# port_expander_1_0.net
KiCad netlist of a schematic drawn in EAGLE
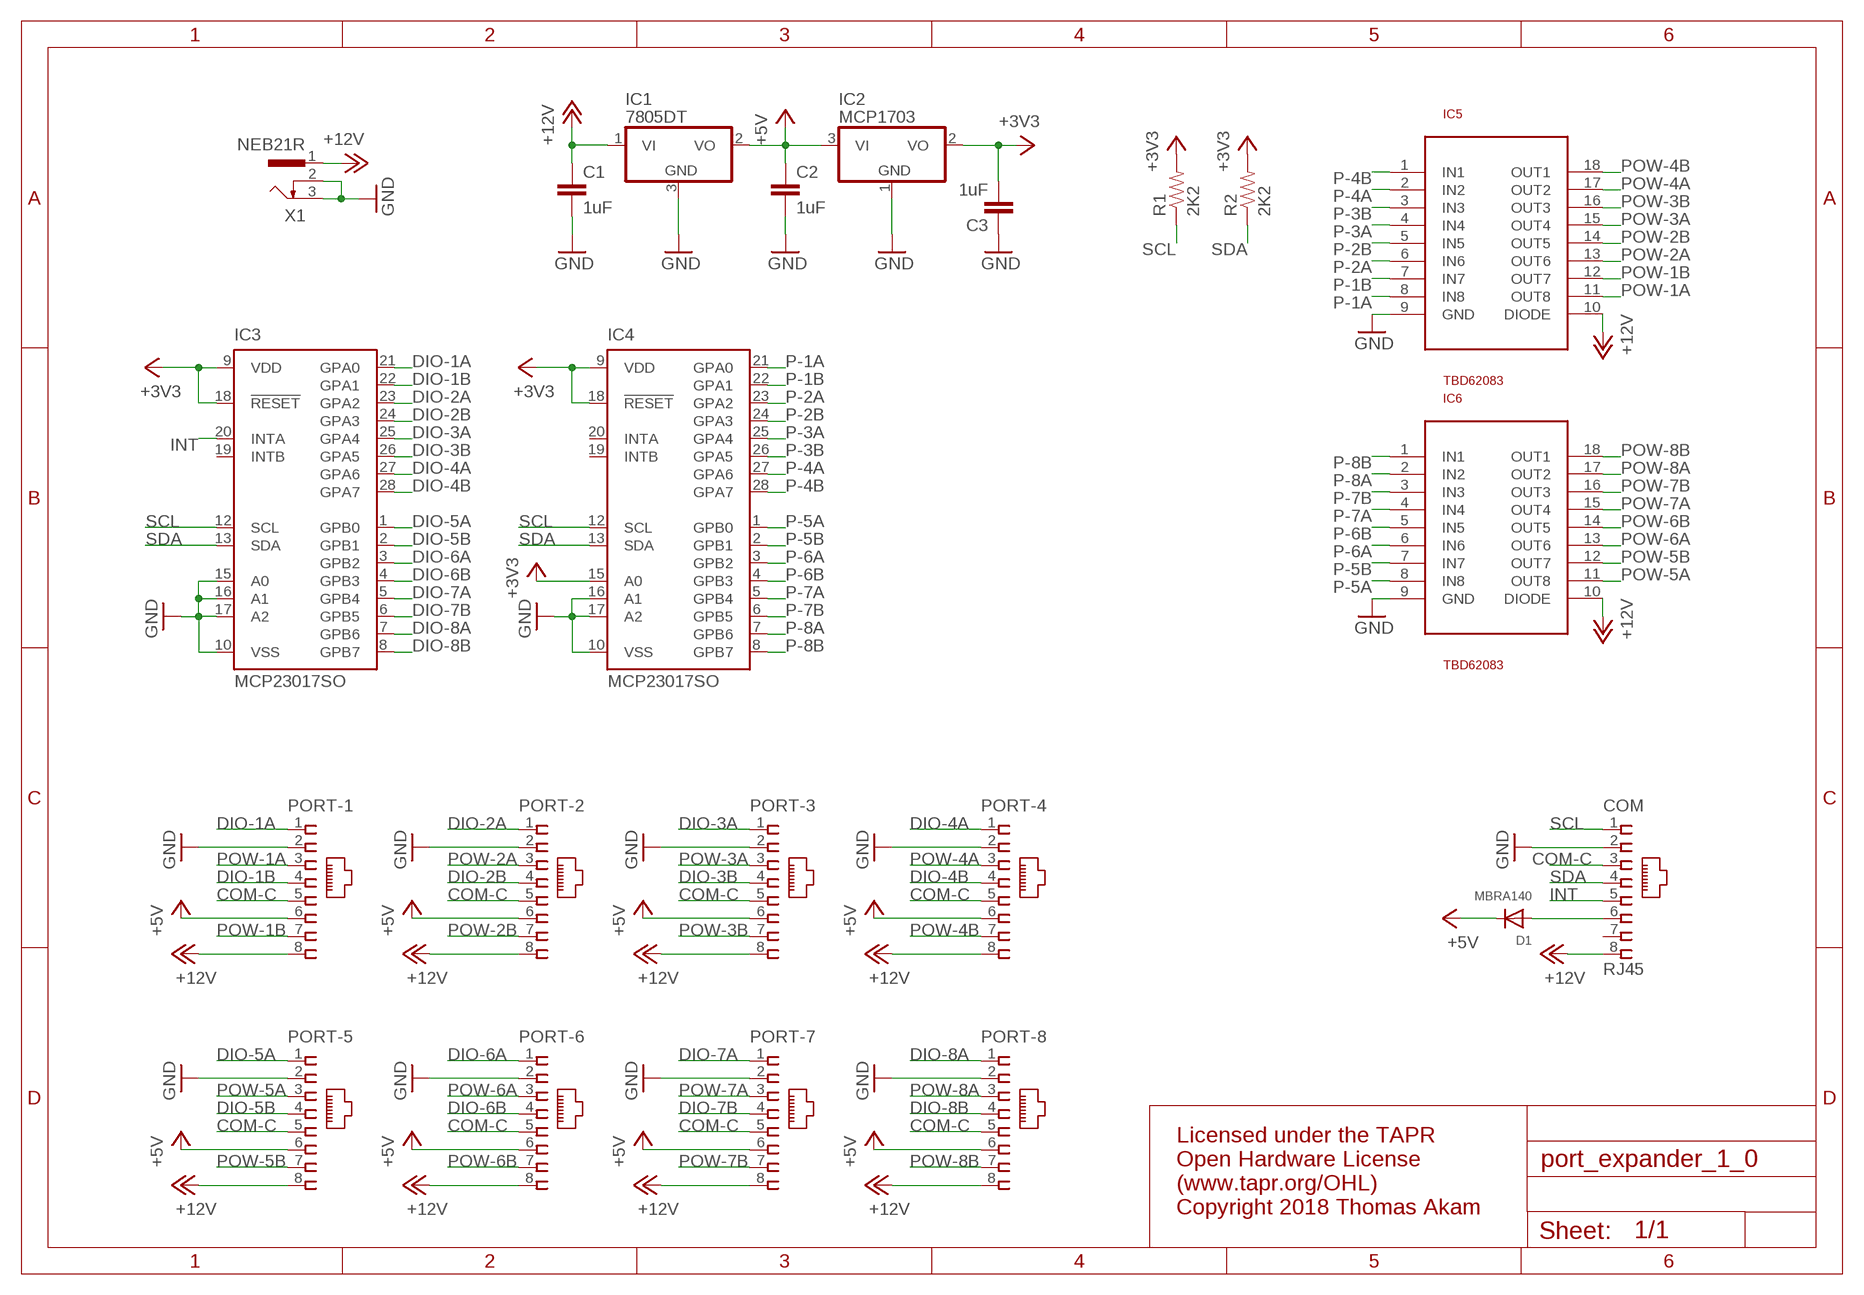
[diagram p0: schematic, sheet 1]

(export (version "E")
  (design (tool "Eeschema 10.0.6"))
  (components
    (comp (ref "C1")
      (value "1uF")
      (footprint "eagle-import:C0805")
      (libsource (lib "eagle-import") (part "resistor_C-EUC0805"))
    )
    (comp (ref "C2")
      (value "1uF")
      (footprint "eagle-import:C0805")
      (libsource (lib "eagle-import") (part "resistor_C-EUC0805"))
    )
    (comp (ref "C3")
      (value "1uF")
      (footprint "eagle-import:C0805")
      (libsource (lib "eagle-import") (part "C-EUC0805"))
    )
    (comp (ref "COM")
      (value "RJ45")
      (footprint "eagle-import:RJ45-NO-SHIELD-VERTICAL")
      (libsource (lib "eagle-import") (part "RJ45VERTICAL"))
    )
    (comp (ref "D1")
      (value "MBRA140")
      (footprint "eagle-import:SOD-123")
      (libsource (lib "eagle-import") (part "DIODESOD-123"))
    )
    (comp (ref "IC1")
      (value "7805DT")
      (footprint "eagle-import:TO252")
      (libsource (lib "eagle-import") (part "78DT05"))
    )
    (comp (ref "IC2")
      (value "MCP1703")
      (footprint "eagle-import:SOT23")
      (libsource (lib "eagle-import") (part "MCP1703CB"))
    )
    (comp (ref "IC3")
      (value "MCP23017SO")
      (footprint "eagle-import:SO28W")
      (fields (field (name "MF") "MICROCHIP") (field (name "MPN") "MCP23017-E/SO"))
      (libsource (lib "eagle-import") (part "MCP23017SO"))
    )
    (comp (ref "IC4")
      (value "MCP23017SO")
      (footprint "eagle-import:SO28W")
      (fields (field (name "MF") "MICROCHIP") (field (name "MPN") "MCP23017-E/SO"))
      (libsource (lib "eagle-import") (part "MCP23017SO"))
    )
    (comp (ref "IC5")
      (value "TBD62083")
      (footprint "eagle-import:SO18L")
      (libsource (lib "eagle-import") (part "ULN2803"))
    )
    (comp (ref "IC6")
      (value "TBD62083")
      (footprint "eagle-import:SO18L")
      (libsource (lib "eagle-import") (part "ULN2803"))
    )
    (comp (ref "PORT-1")
      (value "RJ45VERTICAL")
      (footprint "eagle-import:RJ45-NO-SHIELD-VERTICAL")
      (libsource (lib "eagle-import") (part "RJ45VERTICAL"))
    )
    (comp (ref "PORT-2")
      (value "RJ45VERTICAL")
      (footprint "eagle-import:RJ45-NO-SHIELD-VERTICAL")
      (libsource (lib "eagle-import") (part "RJ45VERTICAL"))
    )
    (comp (ref "PORT-3")
      (value "RJ45VERTICAL")
      (footprint "eagle-import:RJ45-NO-SHIELD-VERTICAL")
      (libsource (lib "eagle-import") (part "RJ45VERTICAL"))
    )
    (comp (ref "PORT-4")
      (value "RJ45VERTICAL")
      (footprint "eagle-import:RJ45-NO-SHIELD-VERTICAL")
      (libsource (lib "eagle-import") (part "RJ45VERTICAL"))
    )
    (comp (ref "PORT-5")
      (value "RJ45VERTICAL")
      (footprint "eagle-import:RJ45-NO-SHIELD-VERTICAL")
      (libsource (lib "eagle-import") (part "RJ45VERTICAL"))
    )
    (comp (ref "PORT-6")
      (value "RJ45VERTICAL")
      (footprint "eagle-import:RJ45-NO-SHIELD-VERTICAL")
      (libsource (lib "eagle-import") (part "RJ45VERTICAL"))
    )
    (comp (ref "PORT-7")
      (value "RJ45VERTICAL")
      (footprint "eagle-import:RJ45-NO-SHIELD-VERTICAL")
      (libsource (lib "eagle-import") (part "RJ45VERTICAL"))
    )
    (comp (ref "PORT-8")
      (value "RJ45VERTICAL")
      (footprint "eagle-import:RJ45-NO-SHIELD-VERTICAL")
      (libsource (lib "eagle-import") (part "RJ45VERTICAL"))
    )
    (comp (ref "R1")
      (value "2K2")
      (footprint "eagle-import:0805")
      (libsource (lib "eagle-import") (part "0.3OHM-1/8W-1%(0805)"))
    )
    (comp (ref "R2")
      (value "2K2")
      (footprint "eagle-import:0805")
      (libsource (lib "eagle-import") (part "0.3OHM-1/8W-1%(0805)"))
    )
    (comp (ref "X1")
      (value "NEB21R")
      (footprint "eagle-import:NEB21R")
      (fields (field (name "MPN") "NEB 21 R"))
      (libsource (lib "eagle-import") (part "NEB21R"))
    )
  )
  (nets
    (net (code "1") (name "+3V3") (class "Default")
      (node (ref "C3") (pin "2") (pinfunction "2_2") (pintype "passive"))
      (node (ref "IC2") (pin "2") (pinfunction "VO_2") (pintype "passive"))
      (node (ref "IC3") (pin "18") (pinfunction "~{RESET}_18") (pintype "input"))
      (node (ref "IC3") (pin "9") (pinfunction "VDD_9") (pintype "power_in"))
      (node (ref "IC4") (pin "15") (pinfunction "A0_15") (pintype "input"))
      (node (ref "IC4") (pin "18") (pinfunction "~{RESET}_18") (pintype "input"))
      (node (ref "IC4") (pin "9") (pinfunction "VDD_9") (pintype "power_in"))
      (node (ref "R1") (pin "2") (pinfunction "2_2") (pintype "passive"))
      (node (ref "R2") (pin "2") (pinfunction "2_2") (pintype "passive"))
    )
    (net (code "2") (name "+5V") (class "Default")
      (node (ref "C2") (pin "1") (pinfunction "1_1") (pintype "passive"))
      (node (ref "D1") (pin "C") (pinfunction "C_C") (pintype "passive"))
      (node (ref "IC1") (pin "2") (pinfunction "VO_2") (pintype "passive"))
      (node (ref "IC2") (pin "3") (pinfunction "VI_3") (pintype "input"))
      (node (ref "PORT-1") (pin "6") (pinfunction "6_6") (pintype "passive"))
      (node (ref "PORT-2") (pin "6") (pinfunction "6_6") (pintype "passive"))
      (node (ref "PORT-3") (pin "6") (pinfunction "6_6") (pintype "passive"))
      (node (ref "PORT-4") (pin "6") (pinfunction "6_6") (pintype "passive"))
      (node (ref "PORT-5") (pin "6") (pinfunction "6_6") (pintype "passive"))
      (node (ref "PORT-6") (pin "6") (pinfunction "6_6") (pintype "passive"))
      (node (ref "PORT-7") (pin "6") (pinfunction "6_6") (pintype "passive"))
      (node (ref "PORT-8") (pin "6") (pinfunction "6_6") (pintype "passive"))
    )
    (net (code "3") (name "+12V") (class "Default")
      (node (ref "C1") (pin "1") (pinfunction "1_1") (pintype "passive"))
      (node (ref "COM") (pin "8") (pinfunction "8_8") (pintype "passive"))
      (node (ref "IC1") (pin "1") (pinfunction "VI_1") (pintype "input"))
      (node (ref "IC5") (pin "10") (pinfunction "DIODE_10") (pintype "power_in"))
      (node (ref "IC6") (pin "10") (pinfunction "DIODE_10") (pintype "power_in"))
      (node (ref "PORT-1") (pin "8") (pinfunction "8_8") (pintype "passive"))
      (node (ref "PORT-2") (pin "8") (pinfunction "8_8") (pintype "passive"))
      (node (ref "PORT-3") (pin "8") (pinfunction "8_8") (pintype "passive"))
      (node (ref "PORT-4") (pin "8") (pinfunction "8_8") (pintype "passive"))
      (node (ref "PORT-5") (pin "8") (pinfunction "8_8") (pintype "passive"))
      (node (ref "PORT-6") (pin "8") (pinfunction "8_8") (pintype "passive"))
      (node (ref "PORT-7") (pin "8") (pinfunction "8_8") (pintype "passive"))
      (node (ref "PORT-8") (pin "8") (pinfunction "8_8") (pintype "passive"))
      (node (ref "X1") (pin "1") (pinfunction "1_1") (pintype "passive"))
    )
    (net (code "4") (name "/COM-C") (class "Default")
      (node (ref "COM") (pin "3") (pinfunction "3_3") (pintype "passive"))
      (node (ref "PORT-1") (pin "5") (pinfunction "5_5") (pintype "passive"))
      (node (ref "PORT-2") (pin "5") (pinfunction "5_5") (pintype "passive"))
      (node (ref "PORT-3") (pin "5") (pinfunction "5_5") (pintype "passive"))
      (node (ref "PORT-4") (pin "5") (pinfunction "5_5") (pintype "passive"))
      (node (ref "PORT-5") (pin "5") (pinfunction "5_5") (pintype "passive"))
      (node (ref "PORT-6") (pin "5") (pinfunction "5_5") (pintype "passive"))
      (node (ref "PORT-7") (pin "5") (pinfunction "5_5") (pintype "passive"))
      (node (ref "PORT-8") (pin "5") (pinfunction "5_5") (pintype "passive"))
    )
    (net (code "5") (name "/DIO-1A") (class "Default")
      (node (ref "IC3") (pin "21") (pinfunction "GPA0_21") (pintype "bidirectional"))
      (node (ref "PORT-1") (pin "1") (pinfunction "1_1") (pintype "passive"))
    )
    (net (code "6") (name "/DIO-1B") (class "Default")
      (node (ref "IC3") (pin "22") (pinfunction "GPA1_22") (pintype "bidirectional"))
      (node (ref "PORT-1") (pin "4") (pinfunction "4_4") (pintype "passive"))
    )
    (net (code "7") (name "/DIO-2A") (class "Default")
      (node (ref "IC3") (pin "23") (pinfunction "GPA2_23") (pintype "bidirectional"))
      (node (ref "PORT-2") (pin "1") (pinfunction "1_1") (pintype "passive"))
    )
    (net (code "8") (name "/DIO-2B") (class "Default")
      (node (ref "IC3") (pin "24") (pinfunction "GPA3_24") (pintype "bidirectional"))
      (node (ref "PORT-2") (pin "4") (pinfunction "4_4") (pintype "passive"))
    )
    (net (code "9") (name "/DIO-3A") (class "Default")
      (node (ref "IC3") (pin "25") (pinfunction "GPA4_25") (pintype "bidirectional"))
      (node (ref "PORT-3") (pin "1") (pinfunction "1_1") (pintype "passive"))
    )
    (net (code "10") (name "/DIO-3B") (class "Default")
      (node (ref "IC3") (pin "26") (pinfunction "GPA5_26") (pintype "bidirectional"))
      (node (ref "PORT-3") (pin "4") (pinfunction "4_4") (pintype "passive"))
    )
    (net (code "11") (name "/DIO-4A") (class "Default")
      (node (ref "IC3") (pin "27") (pinfunction "GPA6_27") (pintype "bidirectional"))
      (node (ref "PORT-4") (pin "1") (pinfunction "1_1") (pintype "passive"))
    )
    (net (code "12") (name "/DIO-4B") (class "Default")
      (node (ref "IC3") (pin "28") (pinfunction "GPA7_28") (pintype "bidirectional"))
      (node (ref "PORT-4") (pin "4") (pinfunction "4_4") (pintype "passive"))
    )
    (net (code "13") (name "/DIO-5A") (class "Default")
      (node (ref "IC3") (pin "1") (pinfunction "GPB0_1") (pintype "bidirectional"))
      (node (ref "PORT-5") (pin "1") (pinfunction "1_1") (pintype "passive"))
    )
    (net (code "14") (name "/DIO-5B") (class "Default")
      (node (ref "IC3") (pin "2") (pinfunction "GPB1_2") (pintype "bidirectional"))
      (node (ref "PORT-5") (pin "4") (pinfunction "4_4") (pintype "passive"))
    )
    (net (code "15") (name "/DIO-6A") (class "Default")
      (node (ref "IC3") (pin "3") (pinfunction "GPB2_3") (pintype "bidirectional"))
      (node (ref "PORT-6") (pin "1") (pinfunction "1_1") (pintype "passive"))
    )
    (net (code "16") (name "/DIO-6B") (class "Default")
      (node (ref "IC3") (pin "4") (pinfunction "GPB3_4") (pintype "bidirectional"))
      (node (ref "PORT-6") (pin "4") (pinfunction "4_4") (pintype "passive"))
    )
    (net (code "17") (name "/DIO-7A") (class "Default")
      (node (ref "IC3") (pin "5") (pinfunction "GPB4_5") (pintype "bidirectional"))
      (node (ref "PORT-7") (pin "1") (pinfunction "1_1") (pintype "passive"))
    )
    (net (code "18") (name "/DIO-7B") (class "Default")
      (node (ref "IC3") (pin "6") (pinfunction "GPB5_6") (pintype "bidirectional"))
      (node (ref "PORT-7") (pin "4") (pinfunction "4_4") (pintype "passive"))
    )
    (net (code "19") (name "/DIO-8A") (class "Default")
      (node (ref "IC3") (pin "7") (pinfunction "GPB6_7") (pintype "bidirectional"))
      (node (ref "PORT-8") (pin "1") (pinfunction "1_1") (pintype "passive"))
    )
    (net (code "20") (name "/DIO-8B") (class "Default")
      (node (ref "IC3") (pin "8") (pinfunction "GPB7_8") (pintype "bidirectional"))
      (node (ref "PORT-8") (pin "4") (pinfunction "4_4") (pintype "passive"))
    )
    (net (code "21") (name "/INT") (class "Default")
      (node (ref "COM") (pin "5") (pinfunction "5_5") (pintype "passive"))
      (node (ref "IC3") (pin "20") (pinfunction "INTA_20") (pintype "output"))
    )
    (net (code "22") (name "/P-1A") (class "Default")
      (node (ref "IC4") (pin "21") (pinfunction "GPA0_21") (pintype "bidirectional"))
      (node (ref "IC5") (pin "8") (pinfunction "IN8_8") (pintype "input"))
    )
    (net (code "23") (name "/P-1B") (class "Default")
      (node (ref "IC4") (pin "22") (pinfunction "GPA1_22") (pintype "bidirectional"))
      (node (ref "IC5") (pin "7") (pinfunction "IN7_7") (pintype "input"))
    )
    (net (code "24") (name "/P-2A") (class "Default")
      (node (ref "IC4") (pin "23") (pinfunction "GPA2_23") (pintype "bidirectional"))
      (node (ref "IC5") (pin "6") (pinfunction "IN6_6") (pintype "input"))
    )
    (net (code "25") (name "/P-2B") (class "Default")
      (node (ref "IC4") (pin "24") (pinfunction "GPA3_24") (pintype "bidirectional"))
      (node (ref "IC5") (pin "5") (pinfunction "IN5_5") (pintype "input"))
    )
    (net (code "26") (name "/P-3A") (class "Default")
      (node (ref "IC4") (pin "25") (pinfunction "GPA4_25") (pintype "bidirectional"))
      (node (ref "IC5") (pin "4") (pinfunction "IN4_4") (pintype "input"))
    )
    (net (code "27") (name "/P-3B") (class "Default")
      (node (ref "IC4") (pin "26") (pinfunction "GPA5_26") (pintype "bidirectional"))
      (node (ref "IC5") (pin "3") (pinfunction "IN3_3") (pintype "input"))
    )
    (net (code "28") (name "/P-4A") (class "Default")
      (node (ref "IC4") (pin "27") (pinfunction "GPA6_27") (pintype "bidirectional"))
      (node (ref "IC5") (pin "2") (pinfunction "IN2_2") (pintype "input"))
    )
    (net (code "29") (name "/P-4B") (class "Default")
      (node (ref "IC4") (pin "28") (pinfunction "GPA7_28") (pintype "bidirectional"))
      (node (ref "IC5") (pin "1") (pinfunction "IN1_1") (pintype "input"))
    )
    (net (code "30") (name "/P-5A") (class "Default")
      (node (ref "IC4") (pin "1") (pinfunction "GPB0_1") (pintype "bidirectional"))
      (node (ref "IC6") (pin "8") (pinfunction "IN8_8") (pintype "input"))
    )
    (net (code "31") (name "/P-5B") (class "Default")
      (node (ref "IC4") (pin "2") (pinfunction "GPB1_2") (pintype "bidirectional"))
      (node (ref "IC6") (pin "7") (pinfunction "IN7_7") (pintype "input"))
    )
    (net (code "32") (name "/P-6A") (class "Default")
      (node (ref "IC4") (pin "3") (pinfunction "GPB2_3") (pintype "bidirectional"))
      (node (ref "IC6") (pin "6") (pinfunction "IN6_6") (pintype "input"))
    )
    (net (code "33") (name "/P-6B") (class "Default")
      (node (ref "IC4") (pin "4") (pinfunction "GPB3_4") (pintype "bidirectional"))
      (node (ref "IC6") (pin "5") (pinfunction "IN5_5") (pintype "input"))
    )
    (net (code "34") (name "/P-7A") (class "Default")
      (node (ref "IC4") (pin "5") (pinfunction "GPB4_5") (pintype "bidirectional"))
      (node (ref "IC6") (pin "4") (pinfunction "IN4_4") (pintype "input"))
    )
    (net (code "35") (name "/P-7B") (class "Default")
      (node (ref "IC4") (pin "6") (pinfunction "GPB5_6") (pintype "bidirectional"))
      (node (ref "IC6") (pin "3") (pinfunction "IN3_3") (pintype "input"))
    )
    (net (code "36") (name "/P-8A") (class "Default")
      (node (ref "IC4") (pin "7") (pinfunction "GPB6_7") (pintype "bidirectional"))
      (node (ref "IC6") (pin "2") (pinfunction "IN2_2") (pintype "input"))
    )
    (net (code "37") (name "/P-8B") (class "Default")
      (node (ref "IC4") (pin "8") (pinfunction "GPB7_8") (pintype "bidirectional"))
      (node (ref "IC6") (pin "1") (pinfunction "IN1_1") (pintype "input"))
    )
    (net (code "38") (name "/POW-1A") (class "Default")
      (node (ref "IC5") (pin "11") (pinfunction "OUT8_11") (pintype "open_collector"))
      (node (ref "PORT-1") (pin "3") (pinfunction "3_3") (pintype "passive"))
    )
    (net (code "39") (name "/POW-1B") (class "Default")
      (node (ref "IC5") (pin "12") (pinfunction "OUT7_12") (pintype "open_collector"))
      (node (ref "PORT-1") (pin "7") (pinfunction "7_7") (pintype "passive"))
    )
    (net (code "40") (name "/POW-2A") (class "Default")
      (node (ref "IC5") (pin "13") (pinfunction "OUT6_13") (pintype "open_collector"))
      (node (ref "PORT-2") (pin "3") (pinfunction "3_3") (pintype "passive"))
    )
    (net (code "41") (name "/POW-2B") (class "Default")
      (node (ref "IC5") (pin "14") (pinfunction "OUT5_14") (pintype "open_collector"))
      (node (ref "PORT-2") (pin "7") (pinfunction "7_7") (pintype "passive"))
    )
    (net (code "42") (name "/POW-3A") (class "Default")
      (node (ref "IC5") (pin "15") (pinfunction "OUT4_15") (pintype "open_collector"))
      (node (ref "PORT-3") (pin "3") (pinfunction "3_3") (pintype "passive"))
    )
    (net (code "43") (name "/POW-3B") (class "Default")
      (node (ref "IC5") (pin "16") (pinfunction "OUT3_16") (pintype "open_collector"))
      (node (ref "PORT-3") (pin "7") (pinfunction "7_7") (pintype "passive"))
    )
    (net (code "44") (name "/POW-4A") (class "Default")
      (node (ref "IC5") (pin "17") (pinfunction "OUT2_17") (pintype "open_collector"))
      (node (ref "PORT-4") (pin "3") (pinfunction "3_3") (pintype "passive"))
    )
    (net (code "45") (name "/POW-4B") (class "Default")
      (node (ref "IC5") (pin "18") (pinfunction "OUT1_18") (pintype "open_collector"))
      (node (ref "PORT-4") (pin "7") (pinfunction "7_7") (pintype "passive"))
    )
    (net (code "46") (name "/POW-5A") (class "Default")
      (node (ref "IC6") (pin "11") (pinfunction "OUT8_11") (pintype "open_collector"))
      (node (ref "PORT-5") (pin "3") (pinfunction "3_3") (pintype "passive"))
    )
    (net (code "47") (name "/POW-5B") (class "Default")
      (node (ref "IC6") (pin "12") (pinfunction "OUT7_12") (pintype "open_collector"))
      (node (ref "PORT-5") (pin "7") (pinfunction "7_7") (pintype "passive"))
    )
    (net (code "48") (name "/POW-6A") (class "Default")
      (node (ref "IC6") (pin "13") (pinfunction "OUT6_13") (pintype "open_collector"))
      (node (ref "PORT-6") (pin "3") (pinfunction "3_3") (pintype "passive"))
    )
    (net (code "49") (name "/POW-6B") (class "Default")
      (node (ref "IC6") (pin "14") (pinfunction "OUT5_14") (pintype "open_collector"))
      (node (ref "PORT-6") (pin "7") (pinfunction "7_7") (pintype "passive"))
    )
    (net (code "50") (name "/POW-7A") (class "Default")
      (node (ref "IC6") (pin "15") (pinfunction "OUT4_15") (pintype "open_collector"))
      (node (ref "PORT-7") (pin "3") (pinfunction "3_3") (pintype "passive"))
    )
    (net (code "51") (name "/POW-7B") (class "Default")
      (node (ref "IC6") (pin "16") (pinfunction "OUT3_16") (pintype "open_collector"))
      (node (ref "PORT-7") (pin "7") (pinfunction "7_7") (pintype "passive"))
    )
    (net (code "52") (name "/POW-8A") (class "Default")
      (node (ref "IC6") (pin "17") (pinfunction "OUT2_17") (pintype "open_collector"))
      (node (ref "PORT-8") (pin "3") (pinfunction "3_3") (pintype "passive"))
    )
    (net (code "53") (name "/POW-8B") (class "Default")
      (node (ref "IC6") (pin "18") (pinfunction "OUT1_18") (pintype "open_collector"))
      (node (ref "PORT-8") (pin "7") (pinfunction "7_7") (pintype "passive"))
    )
    (net (code "54") (name "/SCL") (class "Default")
      (node (ref "COM") (pin "1") (pinfunction "1_1") (pintype "passive"))
      (node (ref "IC3") (pin "12") (pinfunction "SCL_12") (pintype "input"))
      (node (ref "IC4") (pin "12") (pinfunction "SCL_12") (pintype "input"))
      (node (ref "R1") (pin "1") (pinfunction "1_1") (pintype "passive"))
    )
    (net (code "55") (name "/SDA") (class "Default")
      (node (ref "COM") (pin "4") (pinfunction "4_4") (pintype "passive"))
      (node (ref "IC3") (pin "13") (pinfunction "SDA_13") (pintype "bidirectional"))
      (node (ref "IC4") (pin "13") (pinfunction "SDA_13") (pintype "bidirectional"))
      (node (ref "R2") (pin "1") (pinfunction "1_1") (pintype "passive"))
    )
    (net (code "56") (name "GND") (class "Default")
      (node (ref "C1") (pin "2") (pinfunction "2_2") (pintype "passive"))
      (node (ref "C2") (pin "2") (pinfunction "2_2") (pintype "passive"))
      (node (ref "C3") (pin "1") (pinfunction "1_1") (pintype "passive"))
      (node (ref "COM") (pin "2") (pinfunction "2_2") (pintype "passive"))
      (node (ref "IC1") (pin "3") (pinfunction "GND_3") (pintype "passive"))
      (node (ref "IC2") (pin "1") (pinfunction "GND_1") (pintype "passive"))
      (node (ref "IC3") (pin "10") (pinfunction "VSS_10") (pintype "power_in"))
      (node (ref "IC3") (pin "15") (pinfunction "A0_15") (pintype "input"))
      (node (ref "IC3") (pin "16") (pinfunction "A1_16") (pintype "input"))
      (node (ref "IC3") (pin "17") (pinfunction "A2_17") (pintype "input"))
      (node (ref "IC4") (pin "10") (pinfunction "VSS_10") (pintype "power_in"))
      (node (ref "IC4") (pin "16") (pinfunction "A1_16") (pintype "input"))
      (node (ref "IC4") (pin "17") (pinfunction "A2_17") (pintype "input"))
      (node (ref "IC5") (pin "9") (pinfunction "GND_9") (pintype "power_in"))
      (node (ref "IC6") (pin "9") (pinfunction "GND_9") (pintype "power_in"))
      (node (ref "PORT-1") (pin "2") (pinfunction "2_2") (pintype "passive"))
      (node (ref "PORT-2") (pin "2") (pinfunction "2_2") (pintype "passive"))
      (node (ref "PORT-3") (pin "2") (pinfunction "2_2") (pintype "passive"))
      (node (ref "PORT-4") (pin "2") (pinfunction "2_2") (pintype "passive"))
      (node (ref "PORT-5") (pin "2") (pinfunction "2_2") (pintype "passive"))
      (node (ref "PORT-6") (pin "2") (pinfunction "2_2") (pintype "passive"))
      (node (ref "PORT-7") (pin "2") (pinfunction "2_2") (pintype "passive"))
      (node (ref "PORT-8") (pin "2") (pinfunction "2_2") (pintype "passive"))
      (node (ref "X1") (pin "2") (pinfunction "2_2") (pintype "passive"))
      (node (ref "X1") (pin "3") (pinfunction "3_3") (pintype "passive"))
    )
    (net (code "57") (name "Net-(COM-Pad6)") (class "Default")
      (node (ref "COM") (pin "6") (pinfunction "6_6") (pintype "passive"))
      (node (ref "D1") (pin "A") (pinfunction "A_A") (pintype "passive"))
    )
    (net (code "58") (name "unconnected-(COM-Pad7)") (class "Default")
      (node (ref "COM") (pin "7") (pinfunction "7_7") (pintype "passive"))
    )
    (net (code "59") (name "unconnected-(IC3-INTB-Pad19)") (class "Default")
      (node (ref "IC3") (pin "19") (pinfunction "INTB_19") (pintype "output"))
    )
    (net (code "60") (name "unconnected-(IC4-INTA-Pad20)") (class "Default")
      (node (ref "IC4") (pin "20") (pinfunction "INTA_20") (pintype "output"))
    )
    (net (code "61") (name "unconnected-(IC4-INTB-Pad19)") (class "Default")
      (node (ref "IC4") (pin "19") (pinfunction "INTB_19") (pintype "output"))
    )
  )
)
